# EBN_KL27Z4_V04.net
KiCad netlist of a schematic drawn in EAGLE
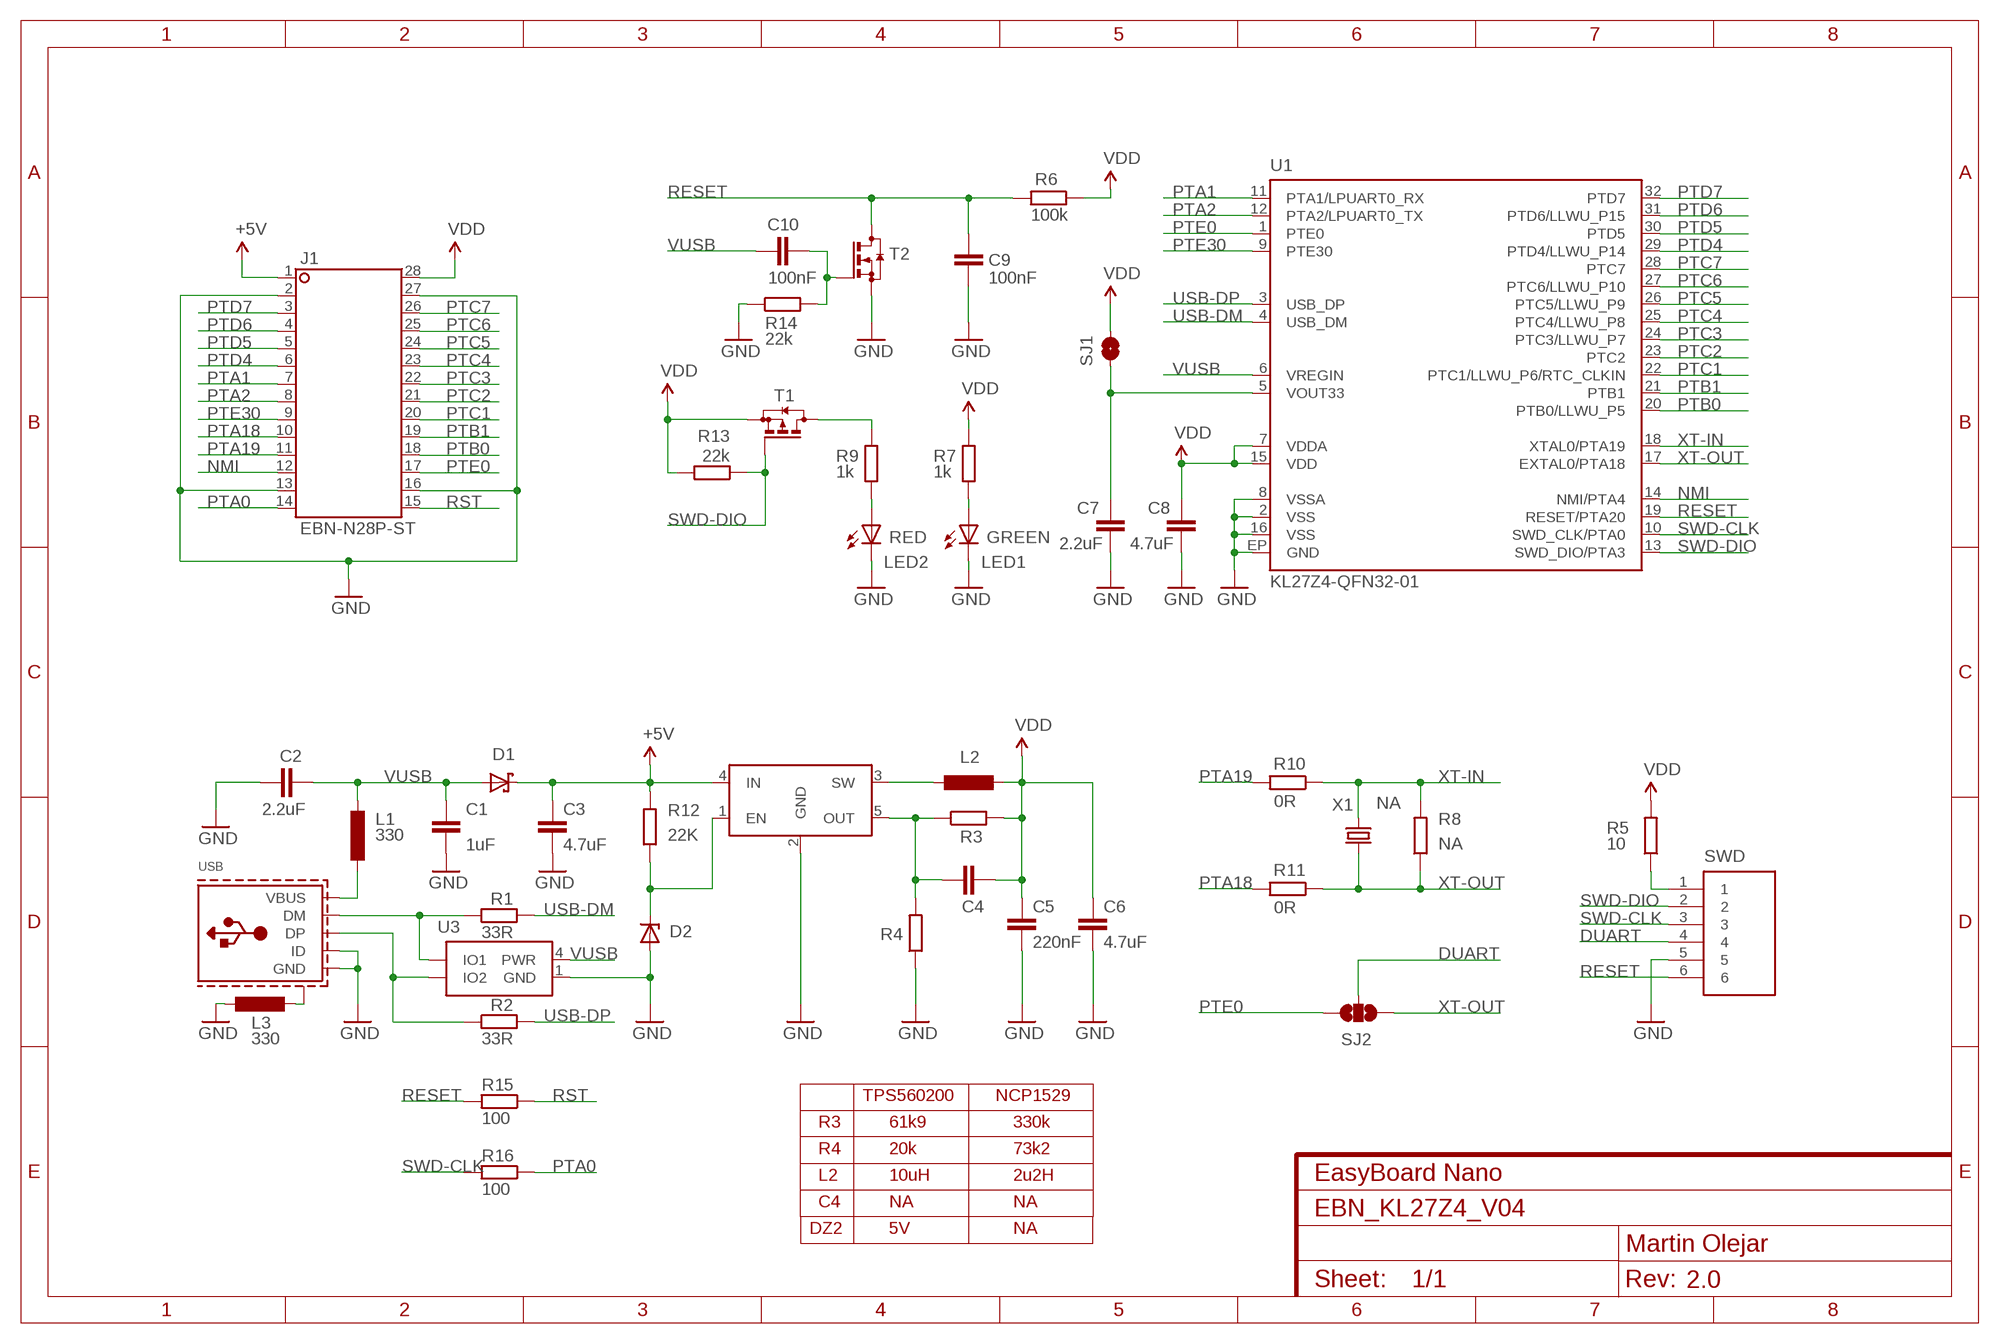
[diagram p0: schematic, sheet 1]

(export (version "E")
  (design (tool "Eeschema 10.0.6"))
  (components
    (comp (ref "C1")
      (value "1uF")
      (footprint "eagle-import:C0402")
      (libsource (lib "eagle-import") (part "C-EUC0402"))
    )
    (comp (ref "C2")
      (value "2.2uF")
      (footprint "eagle-import:C0603")
      (libsource (lib "eagle-import") (part "C-EUC0603"))
    )
    (comp (ref "C3")
      (value "4.7uF")
      (footprint "eagle-import:C0603")
      (libsource (lib "eagle-import") (part "C-EUC0603"))
    )
    (comp (ref "C4")
      (value "*")
      (footprint "eagle-import:C0402")
      (libsource (lib "eagle-import") (part "C-EUC0402"))
    )
    (comp (ref "C5")
      (value "220nF")
      (footprint "eagle-import:C0603")
      (libsource (lib "eagle-import") (part "C-EUC0603"))
    )
    (comp (ref "C6")
      (value "4.7uF")
      (footprint "eagle-import:C0603")
      (libsource (lib "eagle-import") (part "C-EUC0603"))
    )
    (comp (ref "C7")
      (value "2.2uF")
      (footprint "eagle-import:C0603")
      (libsource (lib "eagle-import") (part "C-EUC0603"))
    )
    (comp (ref "C8")
      (value "4.7uF")
      (footprint "eagle-import:C0603")
      (libsource (lib "eagle-import") (part "C-EUC0603"))
    )
    (comp (ref "C9")
      (value "100nF")
      (footprint "eagle-import:C0402")
      (libsource (lib "eagle-import") (part "C-EUC0402"))
    )
    (comp (ref "C10")
      (value "100nF")
      (footprint "eagle-import:C0402")
      (libsource (lib "eagle-import") (part "C-EUC0402"))
    )
    (comp (ref "D1")
      (value "PMEG2010BER_SHOTTKY-SOD123FL")
      (footprint "eagle-import:SOD-123FL")
      (libsource (lib "eagle-import") (part "_SHOTTKY-SOD123FLPMEG2010BER"))
    )
    (comp (ref "D2")
      (value "DZ")
      (footprint "eagle-import:SOD323_ST")
      (libsource (lib "eagle-import") (part "DZ"))
    )
    (comp (ref "J1")
      (value "EBN-N28P-ST")
      (footprint "eagle-import:EBN-N28P-SHIELD")
      (libsource (lib "eagle-import") (part "EBN-N28P-ST"))
    )
    (comp (ref "L1")
      (value "330")
      (footprint "eagle-import:L0805")
      (libsource (lib "eagle-import") (part "L-EUL0805"))
    )
    (comp (ref "L2")
      (value "2u2")
      (footprint "eagle-import:LPS3015")
      (libsource (lib "eagle-import") (part "L-EULPS3015"))
    )
    (comp (ref "L3")
      (value "330")
      (footprint "eagle-import:L0805")
      (libsource (lib "eagle-import") (part "L-EUL0805"))
    )
    (comp (ref "LED1")
      (value "LEDCHIPLED_0603")
      (footprint "eagle-import:CHIPLED_0603")
      (libsource (lib "eagle-import") (part "LEDCHIPLED_0603"))
    )
    (comp (ref "LED2")
      (value "LEDCHIPLED_0603")
      (footprint "eagle-import:CHIPLED_0603")
      (libsource (lib "eagle-import") (part "LEDCHIPLED_0603"))
    )
    (comp (ref "R1")
      (value "33R")
      (footprint "eagle-import:R0603")
      (libsource (lib "eagle-import") (part "R-EUR0603"))
    )
    (comp (ref "R2")
      (value "33R")
      (footprint "eagle-import:R0603")
      (libsource (lib "eagle-import") (part "R-EUR0603"))
    )
    (comp (ref "R3")
      (value "*")
      (footprint "eagle-import:R0402")
      (libsource (lib "eagle-import") (part "R-EUR0402"))
    )
    (comp (ref "R4")
      (value "*")
      (footprint "eagle-import:R0402")
      (libsource (lib "eagle-import") (part "R-EUR0402"))
    )
    (comp (ref "R5")
      (value "10")
      (footprint "eagle-import:R0603")
      (libsource (lib "eagle-import") (part "R-EUR0603"))
    )
    (comp (ref "R6")
      (value "100k")
      (footprint "eagle-import:R0402")
      (libsource (lib "eagle-import") (part "R-EUR0402"))
    )
    (comp (ref "R7")
      (value "1k")
      (footprint "eagle-import:R0402")
      (libsource (lib "eagle-import") (part "R-EUR0402"))
    )
    (comp (ref "R8")
      (value "NA")
      (footprint "eagle-import:R0402")
      (libsource (lib "eagle-import") (part "R-EUR0402"))
    )
    (comp (ref "R9")
      (value "1k")
      (footprint "eagle-import:R0402")
      (libsource (lib "eagle-import") (part "R-EUR0402"))
    )
    (comp (ref "R10")
      (value "0R")
      (footprint "eagle-import:R0402")
      (libsource (lib "eagle-import") (part "R-EUR0402"))
    )
    (comp (ref "R11")
      (value "0R")
      (footprint "eagle-import:R0402")
      (libsource (lib "eagle-import") (part "R-EUR0402"))
    )
    (comp (ref "R12")
      (value "22K")
      (footprint "eagle-import:R0603")
      (libsource (lib "eagle-import") (part "R-EUR0603"))
    )
    (comp (ref "R13")
      (value "22k")
      (footprint "eagle-import:R0402")
      (libsource (lib "eagle-import") (part "R-EUR0402"))
    )
    (comp (ref "R14")
      (value "22k")
      (footprint "eagle-import:R0402")
      (libsource (lib "eagle-import") (part "R-EUR0402"))
    )
    (comp (ref "R15")
      (value "100")
      (footprint "eagle-import:R0402")
      (libsource (lib "eagle-import") (part "R-EUR0402"))
    )
    (comp (ref "R16")
      (value "100")
      (footprint "eagle-import:R0402")
      (libsource (lib "eagle-import") (part "R-EUR0402"))
    )
    (comp (ref "SJ1")
      (value "SJ-S")
      (footprint "eagle-import:JUMPER-SMD-S1X")
      (libsource (lib "eagle-import") (part "SJ-S"))
    )
    (comp (ref "SJ2")
      (value "SJ2W-S")
      (footprint "eagle-import:JUMPER-SMD-S2X")
      (libsource (lib "eagle-import") (part "SJ2W-S"))
    )
    (comp (ref "SWD")
      (value "CON-1X6JST-SIDE")
      (footprint "eagle-import:CON-JST1X6-SIDE")
      (libsource (lib "eagle-import") (part "CON-1X6JST-SIDE"))
    )
    (comp (ref "T1")
      (value "-PMOS-SOT323")
      (footprint "eagle-import:SOT323")
      (libsource (lib "eagle-import") (part "-PMOS-SOT323"))
    )
    (comp (ref "T2")
      (value "-NMOS-SOT323")
      (footprint "eagle-import:SOT323")
      (libsource (lib "eagle-import") (part "-NMOS-SOT323"))
    )
    (comp (ref "U1")
      (value "KL27Z4-QFN32-01")
      (footprint "eagle-import:QFN-32")
      (libsource (lib "eagle-import") (part "KL27Z4-QFN32-01"))
    )
    (comp (ref "U2")
      (value "MP215P")
      (footprint "eagle-import:SOT23-5L")
      (libsource (lib "eagle-import") (part "MP215P"))
    )
    (comp (ref "U3")
      (value "PRTR5V0U2X")
      (footprint "eagle-import:SOT-143B")
      (fields
        (field (name "MANUFACTURER") "NXP Semiconductors")
        (field (name "PART_NUMBER") "PRTR5V0U2X,215")
      )
      (libsource (lib "eagle-import") (part "PRTR5V0U2X?"))
    )
    (comp (ref "USB")
      (value "USB-5P-MICRO-SMD-04")
      (footprint "eagle-import:USB-MICRO-SMD-04")
      (libsource (lib "eagle-import") (part "USB-5P-MICRO-SMD-04"))
    )
    (comp (ref "X1")
      (value "NA")
      (footprint "eagle-import:SMD-2X-3215")
      (libsource (lib "eagle-import") (part "XTAL1-SMD-2P-3.2X1.5MM"))
    )
  )
  (nets
    (net (code "1") (name "+5V") (class "Default")
      (node (ref "C3") (pin "1") (pinfunction "1_1") (pintype "passive"))
      (node (ref "D1") (pin "C") (pinfunction "C_C") (pintype "passive"))
      (node (ref "J1") (pin "1") (pinfunction "1_1") (pintype "passive"))
      (node (ref "R12") (pin "2") (pinfunction "2_2") (pintype "passive"))
      (node (ref "U2") (pin "4") (pinfunction "IN_4") (pintype "power_in"))
    )
    (net (code "2") (name "/DUART") (class "Default")
      (node (ref "SJ2") (pin "2") (pinfunction "2_2") (pintype "passive"))
      (node (ref "SWD") (pin "4") (pinfunction "4_4") (pintype "bidirectional"))
    )
    (net (code "3") (name "/NMI") (class "Default")
      (node (ref "J1") (pin "12") (pinfunction "12_12") (pintype "passive"))
      (node (ref "U1") (pin "14") (pinfunction "NMI/PTA4_14") (pintype "bidirectional"))
    )
    (net (code "4") (name "/PTA0") (class "Default")
      (node (ref "J1") (pin "14") (pinfunction "14_14") (pintype "passive"))
      (node (ref "R16") (pin "1") (pinfunction "1_1") (pintype "passive"))
    )
    (net (code "5") (name "/PTA1") (class "Default")
      (node (ref "J1") (pin "7") (pinfunction "7_7") (pintype "passive"))
      (node (ref "U1") (pin "11") (pinfunction "PTA1/LPUART0_RX_11") (pintype "bidirectional"))
    )
    (net (code "6") (name "/PTA2") (class "Default")
      (node (ref "J1") (pin "8") (pinfunction "8_8") (pintype "passive"))
      (node (ref "U1") (pin "12") (pinfunction "PTA2/LPUART0_TX_12") (pintype "bidirectional"))
    )
    (net (code "7") (name "/PTA18") (class "Default")
      (node (ref "J1") (pin "10") (pinfunction "10_10") (pintype "passive"))
      (node (ref "R11") (pin "2") (pinfunction "2_2") (pintype "passive"))
    )
    (net (code "8") (name "/PTA19") (class "Default")
      (node (ref "J1") (pin "11") (pinfunction "11_11") (pintype "passive"))
      (node (ref "R10") (pin "2") (pinfunction "2_2") (pintype "passive"))
    )
    (net (code "9") (name "/PTB0") (class "Default")
      (node (ref "J1") (pin "18") (pinfunction "18_18") (pintype "passive"))
      (node (ref "U1") (pin "20") (pinfunction "PTB0/LLWU_P5_20") (pintype "bidirectional"))
    )
    (net (code "10") (name "/PTB1") (class "Default")
      (node (ref "J1") (pin "19") (pinfunction "19_19") (pintype "passive"))
      (node (ref "U1") (pin "21") (pinfunction "PTB1_21") (pintype "bidirectional"))
    )
    (net (code "11") (name "/PTC1") (class "Default")
      (node (ref "J1") (pin "20") (pinfunction "20_20") (pintype "passive"))
      (node (ref "U1") (pin "22") (pinfunction "PTC1/LLWU_P6/RTC_CLKIN_22") (pintype "bidirectional"))
    )
    (net (code "12") (name "/PTC2") (class "Default")
      (node (ref "J1") (pin "21") (pinfunction "21_21") (pintype "passive"))
      (node (ref "U1") (pin "23") (pinfunction "PTC2_23") (pintype "bidirectional"))
    )
    (net (code "13") (name "/PTC3") (class "Default")
      (node (ref "J1") (pin "22") (pinfunction "22_22") (pintype "passive"))
      (node (ref "U1") (pin "24") (pinfunction "PTC3/LLWU_P7_24") (pintype "bidirectional"))
    )
    (net (code "14") (name "/PTC4") (class "Default")
      (node (ref "J1") (pin "23") (pinfunction "23_23") (pintype "passive"))
      (node (ref "U1") (pin "25") (pinfunction "PTC4/LLWU_P8_25") (pintype "bidirectional"))
    )
    (net (code "15") (name "/PTC5") (class "Default")
      (node (ref "J1") (pin "24") (pinfunction "24_24") (pintype "passive"))
      (node (ref "U1") (pin "26") (pinfunction "PTC5/LLWU_P9_26") (pintype "bidirectional"))
    )
    (net (code "16") (name "/PTC6") (class "Default")
      (node (ref "J1") (pin "25") (pinfunction "25_25") (pintype "passive"))
      (node (ref "U1") (pin "27") (pinfunction "PTC6/LLWU_P10_27") (pintype "bidirectional"))
    )
    (net (code "17") (name "/PTC7") (class "Default")
      (node (ref "J1") (pin "26") (pinfunction "26_26") (pintype "passive"))
      (node (ref "U1") (pin "28") (pinfunction "PTC7_28") (pintype "bidirectional"))
    )
    (net (code "18") (name "/PTD4") (class "Default")
      (node (ref "J1") (pin "6") (pinfunction "6_6") (pintype "passive"))
      (node (ref "U1") (pin "29") (pinfunction "PTD4/LLWU_P14_29") (pintype "bidirectional"))
    )
    (net (code "19") (name "/PTD5") (class "Default")
      (node (ref "J1") (pin "5") (pinfunction "5_5") (pintype "passive"))
      (node (ref "U1") (pin "30") (pinfunction "PTD5_30") (pintype "bidirectional"))
    )
    (net (code "20") (name "/PTD6") (class "Default")
      (node (ref "J1") (pin "4") (pinfunction "4_4") (pintype "passive"))
      (node (ref "U1") (pin "31") (pinfunction "PTD6/LLWU_P15_31") (pintype "bidirectional"))
    )
    (net (code "21") (name "/PTD7") (class "Default")
      (node (ref "J1") (pin "3") (pinfunction "3_3") (pintype "passive"))
      (node (ref "U1") (pin "32") (pinfunction "PTD7_32") (pintype "bidirectional"))
    )
    (net (code "22") (name "/PTE0") (class "Default")
      (node (ref "J1") (pin "17") (pinfunction "17_17") (pintype "passive"))
      (node (ref "SJ2") (pin "3") (pinfunction "3_3") (pintype "passive"))
      (node (ref "U1") (pin "1") (pinfunction "PTE0_1") (pintype "bidirectional"))
    )
    (net (code "23") (name "/PTE30") (class "Default")
      (node (ref "J1") (pin "9") (pinfunction "9_9") (pintype "passive"))
      (node (ref "U1") (pin "9") (pinfunction "PTE30_9") (pintype "bidirectional"))
    )
    (net (code "24") (name "/RESET") (class "Default")
      (node (ref "C9") (pin "1") (pinfunction "1_1") (pintype "passive"))
      (node (ref "R15") (pin "2") (pinfunction "2_2") (pintype "passive"))
      (node (ref "R6") (pin "2") (pinfunction "2_2") (pintype "passive"))
      (node (ref "SWD") (pin "6") (pinfunction "6_6") (pintype "bidirectional"))
      (node (ref "T2") (pin "3") (pinfunction "D_3") (pintype "passive"))
      (node (ref "U1") (pin "19") (pinfunction "RESET/PTA20_19") (pintype "bidirectional"))
    )
    (net (code "25") (name "/RST") (class "Default")
      (node (ref "J1") (pin "15") (pinfunction "15_15") (pintype "passive"))
      (node (ref "R15") (pin "1") (pinfunction "1_1") (pintype "passive"))
    )
    (net (code "26") (name "/SWD-CLK") (class "Default")
      (node (ref "R16") (pin "2") (pinfunction "2_2") (pintype "passive"))
      (node (ref "SWD") (pin "3") (pinfunction "3_3") (pintype "bidirectional"))
      (node (ref "U1") (pin "10") (pinfunction "SWD_CLK/PTA0_10") (pintype "bidirectional"))
    )
    (net (code "27") (name "/SWD-DIO") (class "Default")
      (node (ref "R13") (pin "1") (pinfunction "1_1") (pintype "passive"))
      (node (ref "SWD") (pin "2") (pinfunction "2_2") (pintype "bidirectional"))
      (node (ref "T1") (pin "1") (pinfunction "G_1") (pintype "passive"))
      (node (ref "U1") (pin "13") (pinfunction "SWD_DIO/PTA3_13") (pintype "bidirectional"))
    )
    (net (code "28") (name "/USB-DM") (class "Default")
      (node (ref "R1") (pin "2") (pinfunction "2_2") (pintype "passive"))
      (node (ref "U1") (pin "4") (pinfunction "USB_DM_4") (pintype "bidirectional"))
    )
    (net (code "29") (name "/USB-DP") (class "Default")
      (node (ref "R2") (pin "2") (pinfunction "2_2") (pintype "passive"))
      (node (ref "U1") (pin "3") (pinfunction "USB_DP_3") (pintype "bidirectional"))
    )
    (net (code "30") (name "/VUSB") (class "Default")
      (node (ref "C1") (pin "2") (pinfunction "2_2") (pintype "passive"))
      (node (ref "C10") (pin "1") (pinfunction "1_1") (pintype "passive"))
      (node (ref "C2") (pin "1") (pinfunction "1_1") (pintype "passive"))
      (node (ref "D1") (pin "A") (pinfunction "A_A") (pintype "passive"))
      (node (ref "L1") (pin "2") (pinfunction "2_2") (pintype "passive"))
      (node (ref "U1") (pin "6") (pinfunction "VREGIN_6") (pintype "power_in"))
      (node (ref "U3") (pin "4") (pinfunction "PWR_4") (pintype "power_in"))
    )
    (net (code "31") (name "/XT-IN") (class "Default")
      (node (ref "R10") (pin "1") (pinfunction "1_1") (pintype "passive"))
      (node (ref "R8") (pin "2") (pinfunction "2_2") (pintype "passive"))
      (node (ref "U1") (pin "18") (pinfunction "XTAL0/PTA19_18") (pintype "bidirectional"))
      (node (ref "X1") (pin "1") (pinfunction "1_1") (pintype "passive"))
    )
    (net (code "32") (name "/XT-OUT") (class "Default")
      (node (ref "R11") (pin "1") (pinfunction "1_1") (pintype "passive"))
      (node (ref "R8") (pin "1") (pinfunction "1_1") (pintype "passive"))
      (node (ref "SJ2") (pin "1") (pinfunction "1_1") (pintype "passive"))
      (node (ref "U1") (pin "17") (pinfunction "EXTAL0/PTA18_17") (pintype "bidirectional"))
      (node (ref "X1") (pin "2") (pinfunction "2_2") (pintype "passive"))
    )
    (net (code "33") (name "GND") (class "Default")
      (node (ref "C1") (pin "1") (pinfunction "1_1") (pintype "passive"))
      (node (ref "C2") (pin "2") (pinfunction "2_2") (pintype "passive"))
      (node (ref "C3") (pin "2") (pinfunction "2_2") (pintype "passive"))
      (node (ref "C5") (pin "2") (pinfunction "2_2") (pintype "passive"))
      (node (ref "C6") (pin "2") (pinfunction "2_2") (pintype "passive"))
      (node (ref "C7") (pin "2") (pinfunction "2_2") (pintype "passive"))
      (node (ref "C8") (pin "2") (pinfunction "2_2") (pintype "passive"))
      (node (ref "C9") (pin "2") (pinfunction "2_2") (pintype "passive"))
      (node (ref "D2") (pin "A") (pinfunction "A_A") (pintype "passive"))
      (node (ref "J1") (pin "13") (pinfunction "13_13") (pintype "passive"))
      (node (ref "J1") (pin "16") (pinfunction "16_16") (pintype "passive"))
      (node (ref "J1") (pin "2") (pinfunction "2_2") (pintype "passive"))
      (node (ref "J1") (pin "27") (pinfunction "27_27") (pintype "passive"))
      (node (ref "L3") (pin "2") (pinfunction "2_2") (pintype "passive"))
      (node (ref "LED1") (pin "C") (pinfunction "C_C") (pintype "passive"))
      (node (ref "LED2") (pin "C") (pinfunction "C_C") (pintype "passive"))
      (node (ref "R14") (pin "1") (pinfunction "1_1") (pintype "passive"))
      (node (ref "R4") (pin "1") (pinfunction "1_1") (pintype "passive"))
      (node (ref "SWD") (pin "5") (pinfunction "5_5") (pintype "bidirectional"))
      (node (ref "T2") (pin "2") (pinfunction "S_2") (pintype "passive"))
      (node (ref "U1") (pin "16") (pinfunction "VSS_16") (pintype "power_in"))
      (node (ref "U1") (pin "2") (pinfunction "VSS_2") (pintype "power_in"))
      (node (ref "U1") (pin "8") (pinfunction "VSSA_8") (pintype "power_in"))
      (node (ref "U1") (pin "EP") (pinfunction "GND_EP") (pintype "power_in"))
      (node (ref "U2") (pin "2") (pinfunction "GND_2") (pintype "power_in"))
      (node (ref "U3") (pin "1") (pinfunction "GND_1") (pintype "power_in"))
      (node (ref "USB") (pin "GND") (pinfunction "GND_GND") (pintype "power_in"))
      (node (ref "USB") (pin "ID") (pinfunction "ID_ID") (pintype "bidirectional"))
    )
    (net (code "34") (name "Net-(L1-Pad1)") (class "Default")
      (node (ref "L1") (pin "1") (pinfunction "1_1") (pintype "passive"))
      (node (ref "USB") (pin "VBUS") (pinfunction "VBUS_VBUS") (pintype "power_in"))
    )
    (net (code "35") (name "Net-(L2-1)") (class "Default")
      (node (ref "L2") (pin "P$1") (pinfunction "1_P$1") (pintype "passive"))
      (node (ref "U2") (pin "3") (pinfunction "SW_3") (pintype "power_in"))
    )
    (net (code "36") (name "Net-(L3-Pad1)") (class "Default")
      (node (ref "L3") (pin "1") (pinfunction "1_1") (pintype "passive"))
      (node (ref "USB") (pin "SHILD@1") (pinfunction "SHILD_SHILD@1") (pintype "passive"))
      (node (ref "USB") (pin "SHILD@2") (pinfunction "SHILD_SHILD@2") (pintype "passive"))
      (node (ref "USB") (pin "SHILD@3") (pinfunction "SHILD_SHILD@3") (pintype "passive"))
      (node (ref "USB") (pin "SHILD@4") (pinfunction "SHILD_SHILD@4") (pintype "passive"))
    )
    (net (code "37") (name "Net-(LED1-PadA)") (class "Default")
      (node (ref "LED1") (pin "A") (pinfunction "A_A") (pintype "passive"))
      (node (ref "R7") (pin "1") (pinfunction "1_1") (pintype "passive"))
    )
    (net (code "38") (name "Net-(LED2-PadA)") (class "Default")
      (node (ref "LED2") (pin "A") (pinfunction "A_A") (pintype "passive"))
      (node (ref "R9") (pin "1") (pinfunction "1_1") (pintype "passive"))
    )
    (net (code "39") (name "Net-(R5-Pad1)") (class "Default")
      (node (ref "R5") (pin "1") (pinfunction "1_1") (pintype "passive"))
      (node (ref "SWD") (pin "1") (pinfunction "1_1") (pintype "bidirectional"))
    )
    (net (code "40") (name "Net-(T1-D)") (class "Default")
      (node (ref "R9") (pin "2") (pinfunction "2_2") (pintype "passive"))
      (node (ref "T1") (pin "3") (pinfunction "D_3") (pintype "passive"))
    )
    (net (code "41") (name "Net-(T2-G)") (class "Default")
      (node (ref "C10") (pin "2") (pinfunction "2_2") (pintype "passive"))
      (node (ref "R14") (pin "2") (pinfunction "2_2") (pintype "passive"))
      (node (ref "T2") (pin "1") (pinfunction "G_1") (pintype "passive"))
    )
    (net (code "42") (name "Net-(U1-VOUT33)") (class "Default")
      (node (ref "C7") (pin "1") (pinfunction "1_1") (pintype "passive"))
      (node (ref "SJ1") (pin "1") (pinfunction "1_1") (pintype "passive"))
      (node (ref "U1") (pin "5") (pinfunction "VOUT33_5") (pintype "power_in"))
    )
    (net (code "43") (name "Net-(U2-EN)") (class "Default")
      (node (ref "D2") (pin "C") (pinfunction "C_C") (pintype "passive"))
      (node (ref "R12") (pin "1") (pinfunction "1_1") (pintype "passive"))
      (node (ref "U2") (pin "1") (pinfunction "EN_1") (pintype "input"))
    )
    (net (code "44") (name "Net-(U2-OUT)") (class "Default")
      (node (ref "C4") (pin "1") (pinfunction "1_1") (pintype "passive"))
      (node (ref "R3") (pin "1") (pinfunction "1_1") (pintype "passive"))
      (node (ref "R4") (pin "2") (pinfunction "2_2") (pintype "passive"))
      (node (ref "U2") (pin "5") (pinfunction "OUT_5") (pintype "output"))
    )
    (net (code "45") (name "Net-(U3-IO1)") (class "Default")
      (node (ref "R1") (pin "1") (pinfunction "1_1") (pintype "passive"))
      (node (ref "U3") (pin "3") (pinfunction "IO1_3") (pintype "bidirectional"))
      (node (ref "USB") (pin "DM") (pinfunction "DM_DM") (pintype "bidirectional"))
    )
    (net (code "46") (name "Net-(U3-IO2)") (class "Default")
      (node (ref "R2") (pin "1") (pinfunction "1_1") (pintype "passive"))
      (node (ref "U3") (pin "2") (pinfunction "IO2_2") (pintype "bidirectional"))
      (node (ref "USB") (pin "DP") (pinfunction "DP_DP") (pintype "bidirectional"))
    )
    (net (code "47") (name "VDD") (class "Default")
      (node (ref "C4") (pin "2") (pinfunction "2_2") (pintype "passive"))
      (node (ref "C5") (pin "1") (pinfunction "1_1") (pintype "passive"))
      (node (ref "C6") (pin "1") (pinfunction "1_1") (pintype "passive"))
      (node (ref "C8") (pin "1") (pinfunction "1_1") (pintype "passive"))
      (node (ref "J1") (pin "28") (pinfunction "28_28") (pintype "passive"))
      (node (ref "L2") (pin "P$2") (pinfunction "2_P$2") (pintype "passive"))
      (node (ref "R13") (pin "2") (pinfunction "2_2") (pintype "passive"))
      (node (ref "R3") (pin "2") (pinfunction "2_2") (pintype "passive"))
      (node (ref "R5") (pin "2") (pinfunction "2_2") (pintype "passive"))
      (node (ref "R6") (pin "1") (pinfunction "1_1") (pintype "passive"))
      (node (ref "R7") (pin "2") (pinfunction "2_2") (pintype "passive"))
      (node (ref "SJ1") (pin "2") (pinfunction "2_2") (pintype "passive"))
      (node (ref "T1") (pin "2") (pinfunction "S_2") (pintype "passive"))
      (node (ref "U1") (pin "15") (pinfunction "VDD_15") (pintype "power_in"))
      (node (ref "U1") (pin "7") (pinfunction "VDDA_7") (pintype "power_in"))
    )
  )
)
